# LEDConverter.net
KiCad netlist of a schematic drawn in Altium Designer
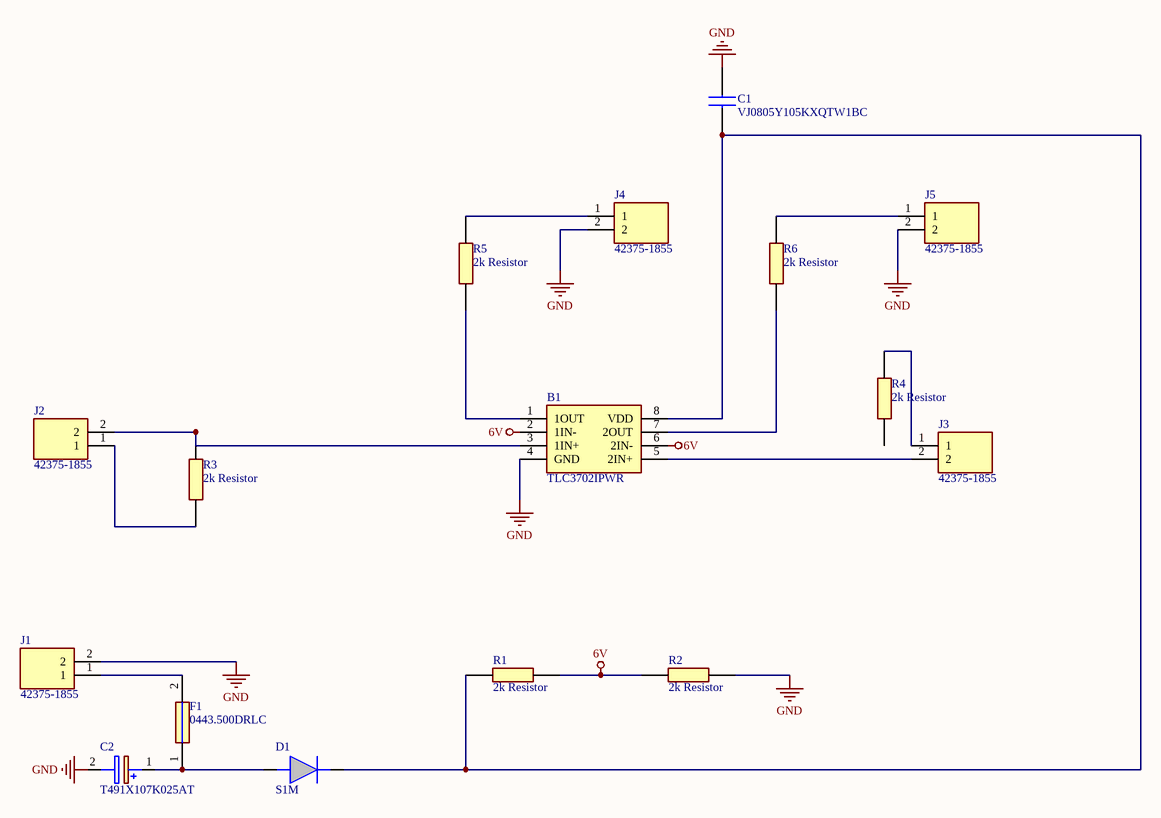
[diagram p0: LEDConverter.SchDoc]

(export (version "E")
  (design (tool "Eeschema 10.0.6"))
  (components
    (comp (ref "B1")
      (value "TLC3702IPWR")
      (footprint "SOP65P640X120-8N")
      (description "Texas Instruments TLC3702IPWR Dual Comparator, Push-Pull O/P, 5 V 8-Pin TSSOP")
      (fields (field (name "MOUSER PART NUMBER") "595-TLC3702IPWR"))
      (libsource (lib "TLC3702IPWR") (part "TLC3702IPWR"))
    )
    (comp (ref "C1")
      (value "VJ0805Y105KXQTW1BC")
      (footprint "CAPC2012X135N")
      (description "Multilayer Ceramic Capacitors MLCC - SMD/SMT 0805 1uF 10volts X7R 10%")
      (fields (field (name "MOUSER PART NUMBER") "77-VJ0805Y105KXQTBC"))
      (libsource (lib "VJ0805Y105KXQTW1BC") (part "VJ0805Y105KXQTW1BC"))
    )
    (comp (ref "C2")
      (value "T491X107K025AT")
      (footprint "SamacSys:T491X")
      (description "Capacitor Polarised")
      (fields (field (name "MOUSER PART NUMBER") "80-T491X107K025AT"))
      (libsource (lib "*") (part "T491X107K025AT"))
    )
    (comp (ref "D1")
      (value "S1M")
      (footprint "DIOM5227X270N")
      (description "Glass passivated junction.; Low profile package.")
      (fields (field (name "MOUSER PART NUMBER") "512-S1M"))
      (libsource (lib "S1M") (part "S1M"))
    )
    (comp (ref "F1")
      (value "0443.500DRLC")
      (footprint "SamacSys:0443500DR")
      (description "Fuse")
      (fields (field (name "MOUSER PART NUMBER") "576-0443.500DRLC"))
      (libsource (lib "*") (part "0443.500DRLC"))
    )
    (comp (ref "J1")
      (value "42375-1855")
      (footprint "HDRV2W87P0X254_1X2_768X249X1494P")
      (description "Headers & Wire Housings KK 100 Hdr Assy Bkw 02 Ckt Tin")
      (fields (field (name "MOUSER PART NUMBER") "538-42375-1855"))
      (libsource (lib "") (part "42375-1855_1"))
    )
    (comp (ref "J2")
      (value "42375-1855")
      (footprint "HDRV2W87P0X254_1X2_768X249X1494P")
      (description "Headers & Wire Housings KK 100 Hdr Assy Bkw 02 Ckt Tin")
      (fields (field (name "MOUSER PART NUMBER") "538-42375-1855"))
      (libsource (lib "") (part "42375-1855_1"))
    )
    (comp (ref "J3")
      (value "42375-1855")
      (footprint "HDRV2W87P0X254_1X2_768X249X1494P")
      (description "Headers & Wire Housings KK 100 Hdr Assy Bkw 02 Ckt Tin")
      (fields (field (name "MOUSER PART NUMBER") "538-42375-1855"))
      (libsource (lib "42375-1855") (part "42375-1855"))
    )
    (comp (ref "J4")
      (value "42375-1855")
      (footprint "HDRV2W87P0X254_1X2_768X249X1494P")
      (description "Headers & Wire Housings KK 100 Hdr Assy Bkw 02 Ckt Tin")
      (fields (field (name "MOUSER PART NUMBER") "538-42375-1855"))
      (libsource (lib "42375-1855") (part "42375-1855"))
    )
    (comp (ref "J5")
      (value "42375-1855")
      (footprint "HDRV2W87P0X254_1X2_768X249X1494P")
      (description "Headers & Wire Housings KK 100 Hdr Assy Bkw 02 Ckt Tin")
      (fields (field (name "MOUSER PART NUMBER") "538-42375-1855"))
      (libsource (lib "42375-1855") (part "42375-1855"))
    )
    (comp (ref "R1")
      (value "2k Resistor")
      (footprint "ERA6AEB101V")
      (description "Metal Thin Film Chip Resistor, 0805, 0.125W")
      (fields (field (name "MANUFACTURER_PART_NUMBER") "ERA-6AED4990V"))
      (libsource (lib "") (part "ERA-6AED4990V_1"))
    )
    (comp (ref "R2")
      (value "2k Resistor")
      (footprint "ERA6AEB101V")
      (description "Metal Thin Film Chip Resistor, 0805, 0.125W")
      (fields (field (name "MANUFACTURER_PART_NUMBER") "ERA-6AED4990V"))
      (libsource (lib "") (part "ERA-6AED4990V_1"))
    )
    (comp (ref "R3")
      (value "2k Resistor")
      (footprint "ERA6AEB101V")
      (description "Metal Thin Film Chip Resistor, 0805, 0.125W")
      (fields (field (name "MANUFACTURER_PART_NUMBER") "ERA-6AED4990V"))
      (libsource (lib "ERA-6AED4990V") (part "ERA-6AED4990V"))
    )
    (comp (ref "R4")
      (value "2k Resistor")
      (footprint "ERA6AEB101V")
      (description "Metal Thin Film Chip Resistor, 0805, 0.125W")
      (fields (field (name "MANUFACTURER_PART_NUMBER") "ERA-6AED4990V"))
      (libsource (lib "ERA-6AED4990V") (part "ERA-6AED4990V"))
    )
    (comp (ref "R5")
      (value "2k Resistor")
      (footprint "ERA6AEB101V")
      (description "Metal Thin Film Chip Resistor, 0805, 0.125W")
      (fields (field (name "MANUFACTURER_PART_NUMBER") "ERA-6AED4990V"))
      (libsource (lib "ERA-6AED4990V") (part "ERA-6AED4990V"))
    )
    (comp (ref "R6")
      (value "2k Resistor")
      (footprint "ERA6AEB101V")
      (description "Metal Thin Film Chip Resistor, 0805, 0.125W")
      (fields (field (name "MANUFACTURER_PART_NUMBER") "ERA-6AED4990V"))
      (libsource (lib "ERA-6AED4990V") (part "ERA-6AED4990V"))
    )
  )
  (nets
    (net (code "1") (name "6V") (class "Default")
      (node (ref "B1") (pin "2") (pinfunction "1IN-_2") (pintype "passive"))
      (node (ref "B1") (pin "6") (pinfunction "2IN-_6") (pintype "passive"))
      (node (ref "R1") (pin "2") (pinfunction "2_2") (pintype "passive"))
      (node (ref "R2") (pin "1") (pinfunction "1_1") (pintype "passive"))
    )
    (net (code "2") (name "GND") (class "Default")
      (node (ref "B1") (pin "4") (pinfunction "GND_4") (pintype "passive"))
      (node (ref "C1") (pin "2") (pinfunction "2_2") (pintype "passive"))
      (node (ref "C2") (pin "2") (pinfunction "-_2") (pintype "passive"))
      (node (ref "J1") (pin "2") (pinfunction "2_2") (pintype "passive"))
      (node (ref "J4") (pin "2") (pinfunction "2_2") (pintype "passive"))
      (node (ref "J5") (pin "2") (pinfunction "2_2") (pintype "passive"))
      (node (ref "R2") (pin "2") (pinfunction "2_2") (pintype "passive"))
    )
    (net (code "3") (name "Net-(B1-1IN+)") (class "Default")
      (node (ref "B1") (pin "3") (pinfunction "1IN+_3") (pintype "passive"))
      (node (ref "J2") (pin "2") (pinfunction "2_2") (pintype "passive"))
      (node (ref "R3") (pin "2") (pinfunction "2_2") (pintype "passive"))
    )
    (net (code "4") (name "Net-(B1-1OUT)") (class "Default")
      (node (ref "B1") (pin "1") (pinfunction "1OUT_1") (pintype "passive"))
      (node (ref "R5") (pin "1") (pinfunction "1_1") (pintype "passive"))
    )
    (net (code "5") (name "Net-(B1-2IN+)") (class "Default")
      (node (ref "B1") (pin "5") (pinfunction "2IN+_5") (pintype "passive"))
      (node (ref "J3") (pin "2") (pinfunction "2_2") (pintype "passive"))
    )
    (net (code "6") (name "Net-(B1-2OUT)") (class "Default")
      (node (ref "B1") (pin "7") (pinfunction "2OUT_7") (pintype "passive"))
      (node (ref "R6") (pin "1") (pinfunction "1_1") (pintype "passive"))
    )
    (net (code "7") (name "Net-(B1-VDD)") (class "Default")
      (node (ref "B1") (pin "8") (pinfunction "VDD_8") (pintype "passive"))
      (node (ref "C1") (pin "1") (pinfunction "1_1") (pintype "passive"))
      (node (ref "D1") (pin "1") (pinfunction "K_1") (pintype "passive"))
      (node (ref "R1") (pin "1") (pinfunction "1_1") (pintype "passive"))
    )
    (net (code "8") (name "Net-(C2-+)") (class "Default")
      (node (ref "C2") (pin "1") (pinfunction "+_1") (pintype "passive"))
      (node (ref "D1") (pin "2") (pinfunction "A_2") (pintype "passive"))
      (node (ref "F1") (pin "1") (pinfunction "1_1") (pintype "passive"))
    )
    (net (code "9") (name "Net-(F1-Pad2)") (class "Default")
      (node (ref "F1") (pin "2") (pinfunction "2_2") (pintype "passive"))
      (node (ref "J1") (pin "1") (pinfunction "1_1") (pintype "passive"))
    )
    (net (code "10") (name "Net-(J2-Pad1)") (class "Default")
      (node (ref "J2") (pin "1") (pinfunction "1_1") (pintype "passive"))
      (node (ref "R3") (pin "1") (pinfunction "1_1") (pintype "passive"))
    )
    (net (code "11") (name "Net-(J3-Pad1)") (class "Default")
      (node (ref "J3") (pin "1") (pinfunction "1_1") (pintype "passive"))
      (node (ref "R4") (pin "2") (pinfunction "2_2") (pintype "passive"))
    )
    (net (code "12") (name "Net-(J4-Pad1)") (class "Default")
      (node (ref "J4") (pin "1") (pinfunction "1_1") (pintype "passive"))
      (node (ref "R5") (pin "2") (pinfunction "2_2") (pintype "passive"))
    )
    (net (code "13") (name "Net-(J5-Pad1)") (class "Default")
      (node (ref "J5") (pin "1") (pinfunction "1_1") (pintype "passive"))
      (node (ref "R6") (pin "2") (pinfunction "2_2") (pintype "passive"))
    )
    (net (code "14") (name "unconnected-(R4-Pad1)") (class "Default")
      (node (ref "R4") (pin "1") (pinfunction "1_1") (pintype "passive"))
    )
  )
)
